# BUTTONS.net
KiCad netlist of a schematic drawn in Altium Designer
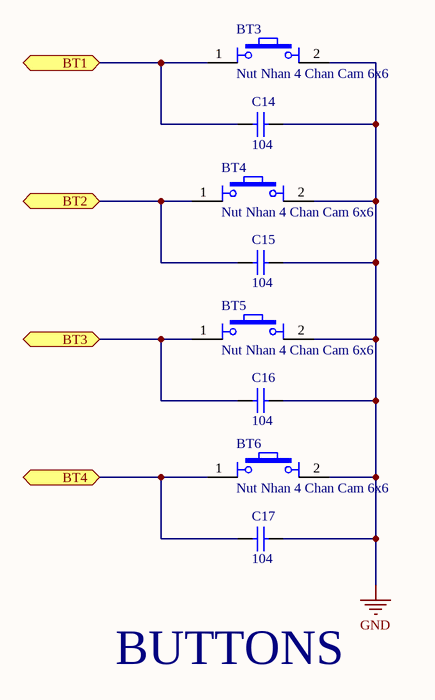
[diagram p0: BUTTONS.SchDoc]

(export (version "E")
  (design (tool "Eeschema 10.0.6"))
  (components
    (comp (ref "BT3")
      (value "Nut Nhan 4 Chan Cam 6x6")
      (footprint "Nut Nhan 4 Chan Cam 6x6")
      (description "Nut Nhan 4 Chan 6x6mm")
      (libsource (lib "Altium_Lib_by_KhueNguyenCreator") (part "Nut Nhan 4 Chan Cam 6x6"))
    )
    (comp (ref "BT4")
      (value "Nut Nhan 4 Chan Cam 6x6")
      (footprint "Nut Nhan 4 Chan Cam 6x6")
      (description "Nut Nhan 4 Chan 6x6mm")
      (libsource (lib "Altium_Lib_by_KhueNguyenCreator") (part "Nut Nhan 4 Chan Cam 6x6"))
    )
    (comp (ref "BT5")
      (value "Nut Nhan 4 Chan Cam 6x6")
      (footprint "Nut Nhan 4 Chan Cam 6x6")
      (description "Nut Nhan 4 Chan 6x6mm")
      (libsource (lib "Altium_Lib_by_KhueNguyenCreator") (part "Nut Nhan 4 Chan Cam 6x6"))
    )
    (comp (ref "BT6")
      (value "Nut Nhan 4 Chan Cam 6x6")
      (footprint "Nut Nhan 4 Chan Cam 6x6")
      (description "Nut Nhan 4 Chan 6x6mm")
      (libsource (lib "Altium_Lib_by_KhueNguyenCreator") (part "Nut Nhan 4 Chan Cam 6x6"))
    )
    (comp (ref "C14")
      (value "104")
      (footprint "tu 0603")
      (description "Dán")
      (libsource (lib "Altium_Lib_by_KhueNguyenCreator") (part "Tu 0603 104 50V 10%"))
    )
    (comp (ref "C15")
      (value "104")
      (footprint "tu 0603")
      (description "Dán")
      (libsource (lib "Altium_Lib_by_KhueNguyenCreator") (part "Tu 0603 104 50V 10%"))
    )
    (comp (ref "C16")
      (value "104")
      (footprint "tu 0603")
      (description "Dán")
      (libsource (lib "Altium_Lib_by_KhueNguyenCreator") (part "Tu 0603 104 50V 10%"))
    )
    (comp (ref "C17")
      (value "104")
      (footprint "tu 0603")
      (description "Dán")
      (libsource (lib "Altium_Lib_by_KhueNguyenCreator") (part "Tu 0603 104 50V 10%"))
    )
  )
  (nets
    (net (code "1") (name "/BT1") (class "Default")
      (node (ref "BT3") (pin "1") (pintype "passive"))
      (node (ref "C14") (pin "1") (pinfunction "1_1") (pintype "passive"))
    )
    (net (code "2") (name "/BT2") (class "Default")
      (node (ref "BT4") (pin "1") (pintype "passive"))
      (node (ref "C15") (pin "1") (pinfunction "1_1") (pintype "passive"))
    )
    (net (code "3") (name "/BT3") (class "Default")
      (node (ref "BT5") (pin "1") (pintype "passive"))
      (node (ref "C16") (pin "1") (pinfunction "1_1") (pintype "passive"))
    )
    (net (code "4") (name "/BT4") (class "Default")
      (node (ref "BT6") (pin "1") (pintype "passive"))
      (node (ref "C17") (pin "1") (pinfunction "1_1") (pintype "passive"))
    )
    (net (code "5") (name "GND") (class "Default")
      (node (ref "BT3") (pin "2") (pintype "passive"))
      (node (ref "BT4") (pin "2") (pintype "passive"))
      (node (ref "BT5") (pin "2") (pintype "passive"))
      (node (ref "BT6") (pin "2") (pintype "passive"))
      (node (ref "C14") (pin "2") (pinfunction "2_2") (pintype "passive"))
      (node (ref "C15") (pin "2") (pinfunction "2_2") (pintype "passive"))
      (node (ref "C16") (pin "2") (pinfunction "2_2") (pintype "passive"))
      (node (ref "C17") (pin "2") (pinfunction "2_2") (pintype "passive"))
    )
  )
)
